# board_full.net
KiCad netlist of a schematic drawn in EAGLE
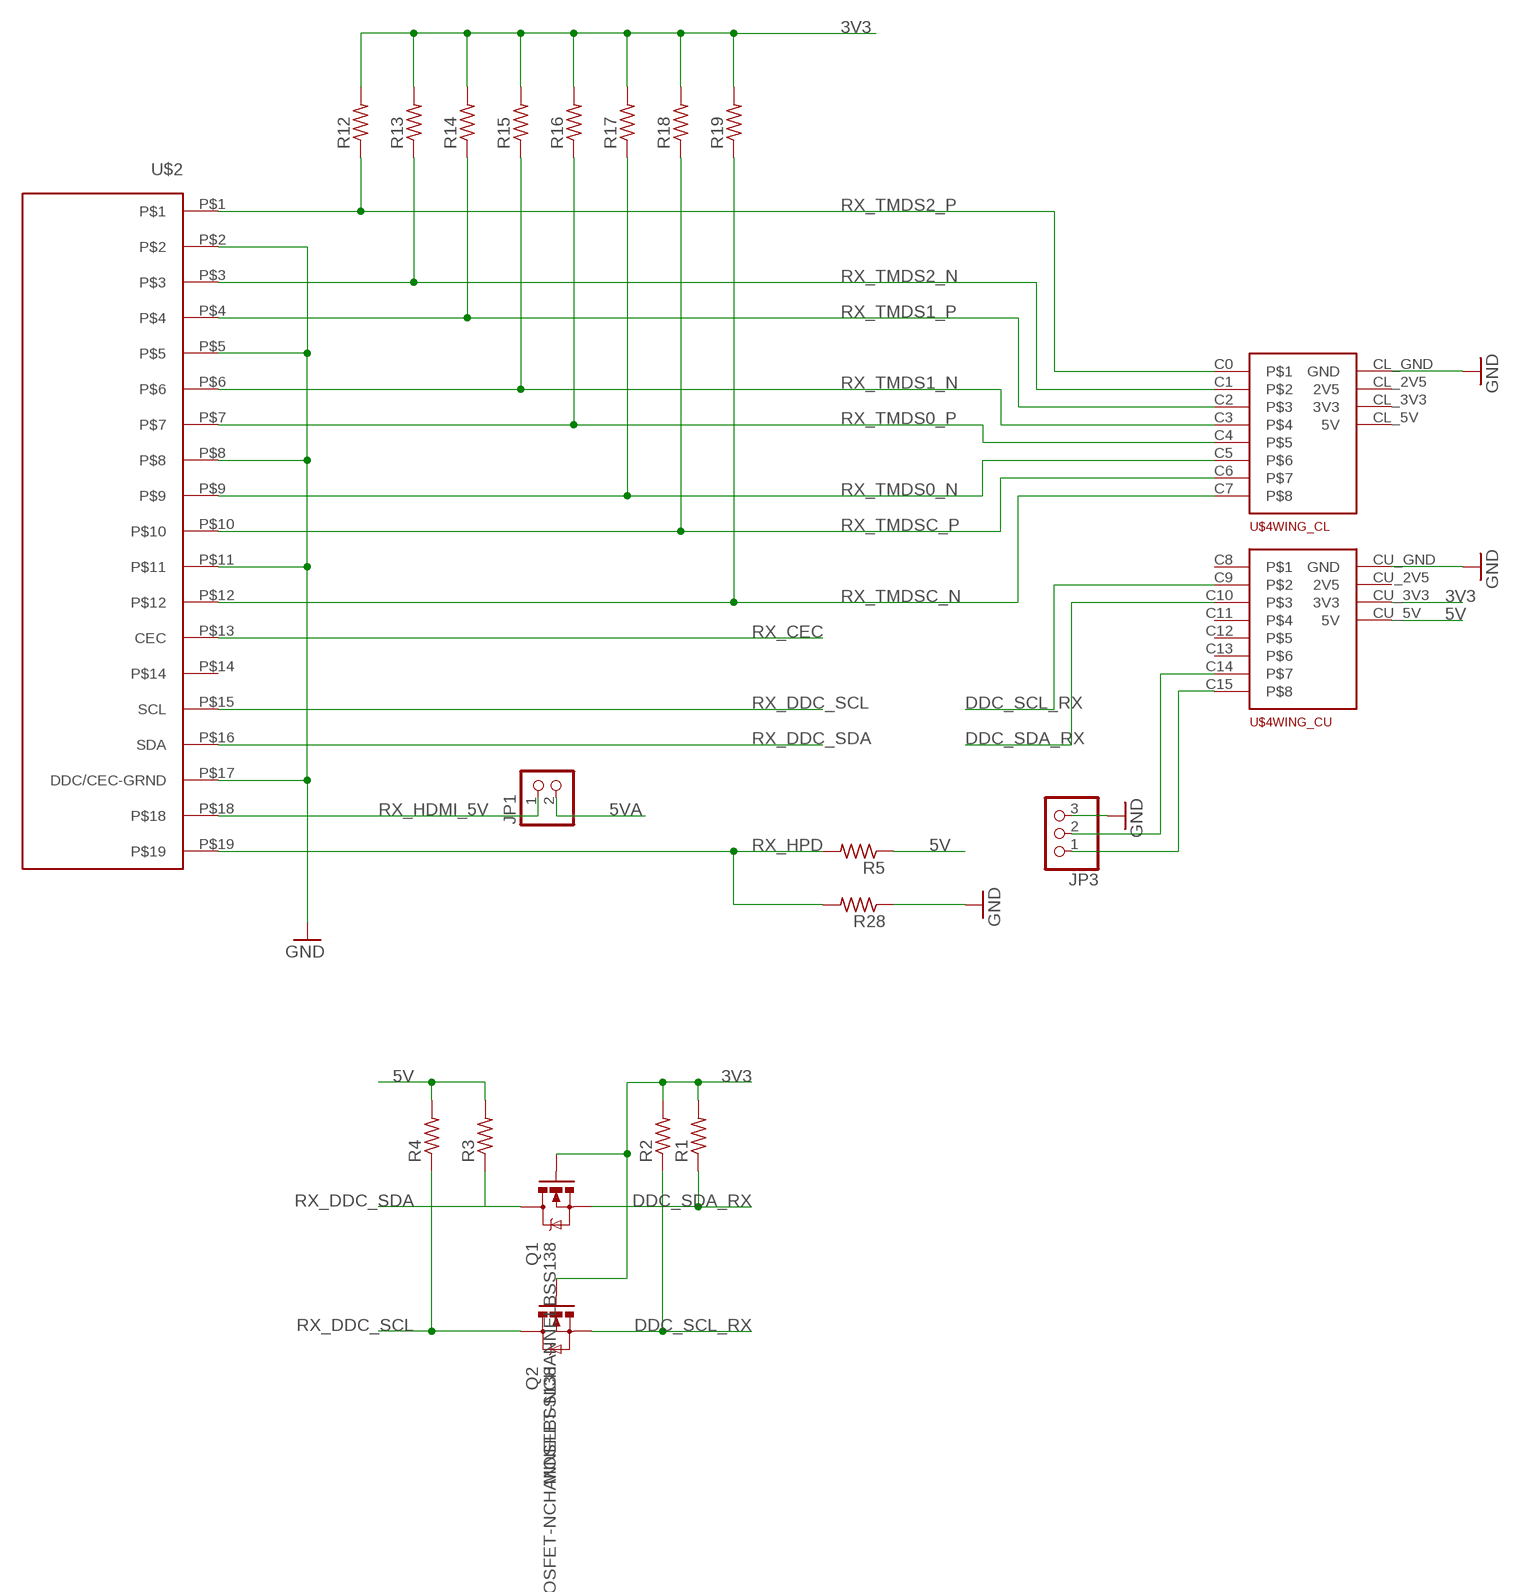
[diagram p0: schematic, sheet 1, part 1 of 2]
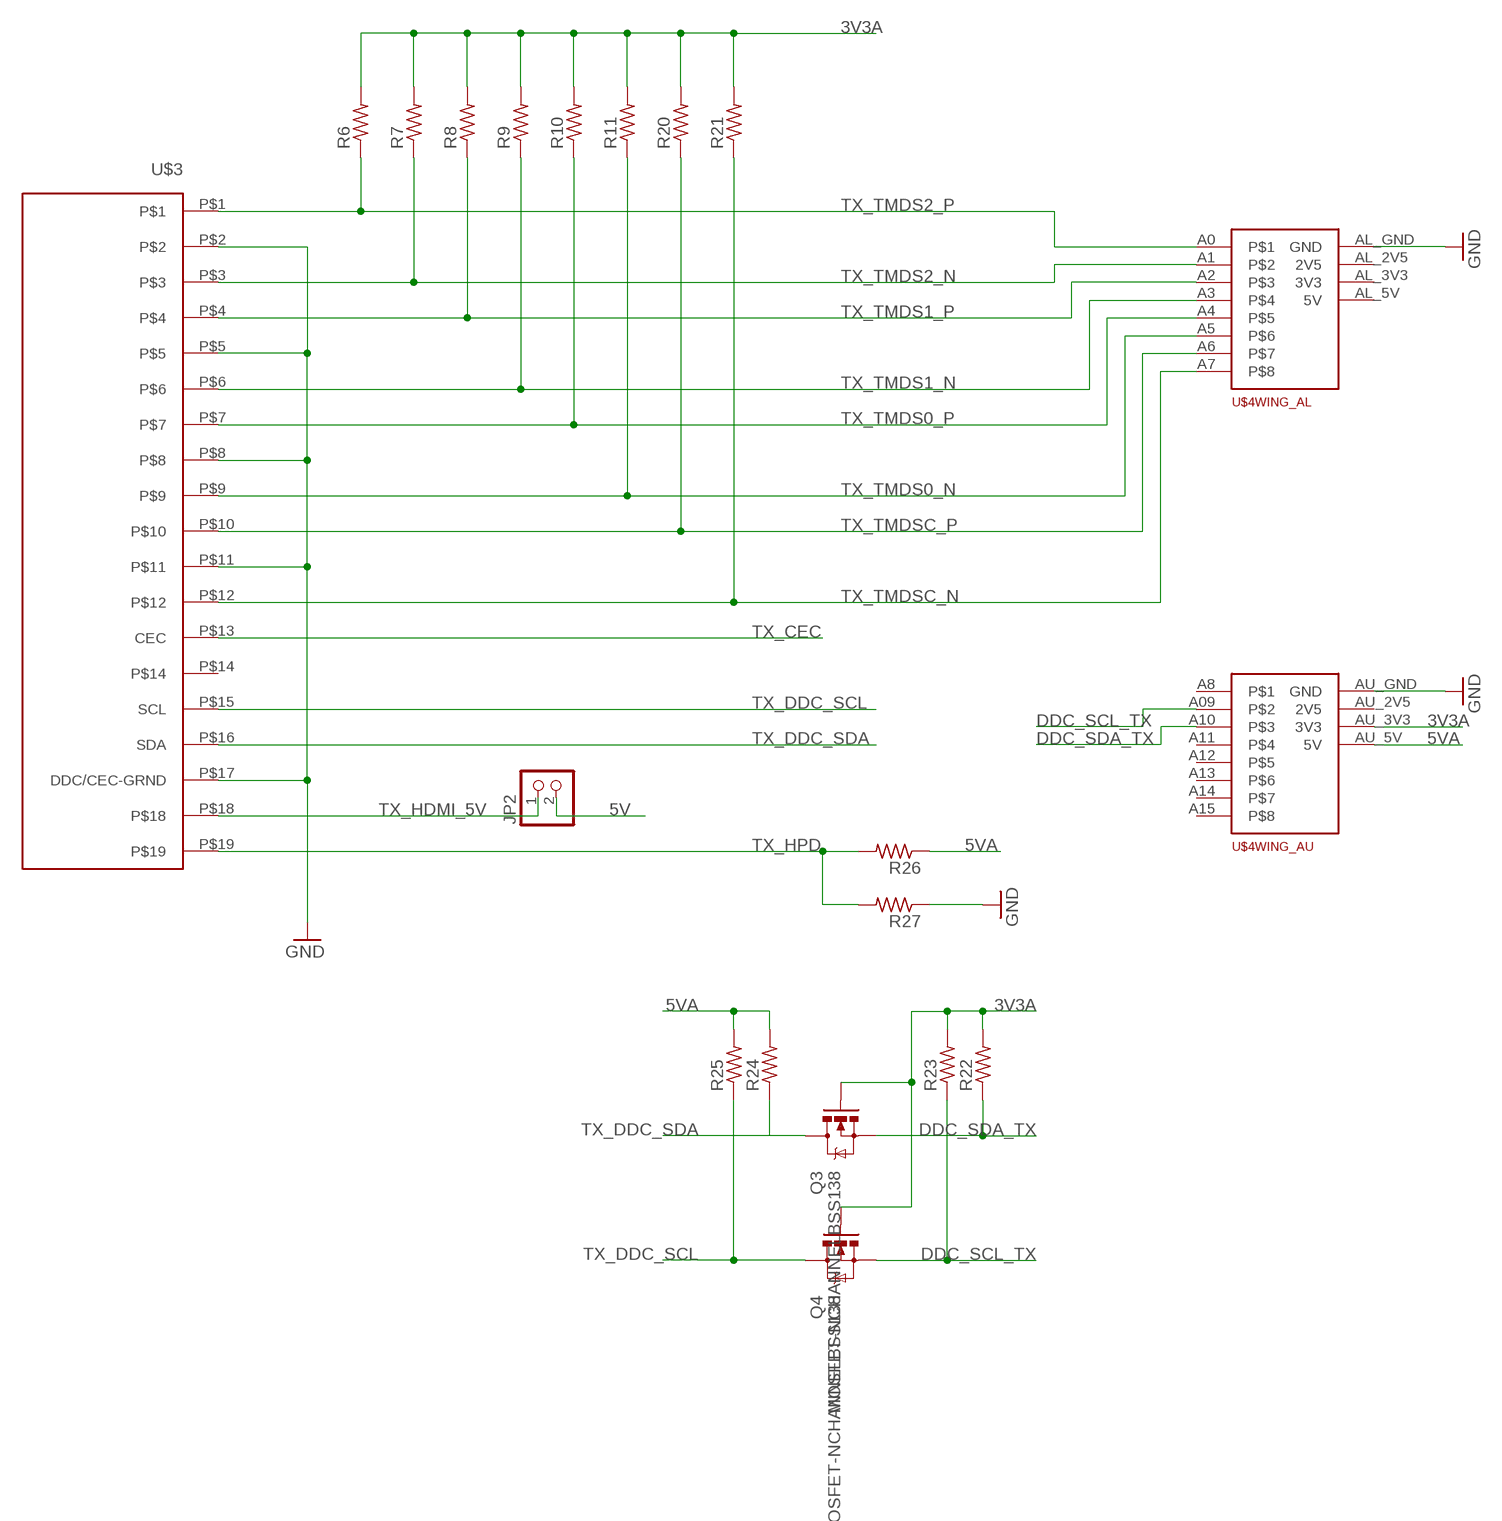
[diagram p1: schematic, sheet 1, part 2 of 2]

(export (version "E")
  (design (tool "Eeschema 10.0.6"))
  (components
    (comp (ref "JP1")
      (value "PINHD-1X2")
      (footprint "eagle-import:1X02")
      (libsource (lib "eagle-import") (part "PINHD-1X2"))
    )
    (comp (ref "JP2")
      (value "PINHD-1X2")
      (footprint "eagle-import:1X02")
      (libsource (lib "eagle-import") (part "PINHD-1X2"))
    )
    (comp (ref "JP3")
      (value "PINHD-1X3")
      (footprint "eagle-import:1X03")
      (libsource (lib "eagle-import") (part "PINHD-1X3"))
    )
    (comp (ref "Q1")
      (value "MOSFET-NCHANNELBSS138")
      (footprint "eagle-import:SOT23")
      (libsource (lib "eagle-import") (part "MOSFET-NCHANNELBSS138"))
    )
    (comp (ref "Q2")
      (value "MOSFET-NCHANNELBSS138")
      (footprint "eagle-import:SOT23")
      (libsource (lib "eagle-import") (part "MOSFET-NCHANNELBSS138"))
    )
    (comp (ref "Q3")
      (value "MOSFET-NCHANNELBSS138")
      (footprint "eagle-import:SOT23")
      (libsource (lib "eagle-import") (part "MOSFET-NCHANNELBSS138"))
    )
    (comp (ref "Q4")
      (value "MOSFET-NCHANNELBSS138")
      (footprint "eagle-import:SOT23")
      (libsource (lib "eagle-import") (part "MOSFET-NCHANNELBSS138"))
    )
    (comp (ref "R1")
      (value "R-US_R0805")
      (footprint "eagle-import:R0805")
      (libsource (lib "eagle-import") (part "R-US_R0805"))
    )
    (comp (ref "R2")
      (value "R-US_R0805")
      (footprint "eagle-import:R0805")
      (libsource (lib "eagle-import") (part "R-US_R0805"))
    )
    (comp (ref "R3")
      (value "R-US_R0805")
      (footprint "eagle-import:R0805")
      (libsource (lib "eagle-import") (part "R-US_R0805"))
    )
    (comp (ref "R4")
      (value "R-US_R0805")
      (footprint "eagle-import:R0805")
      (libsource (lib "eagle-import") (part "R-US_R0805"))
    )
    (comp (ref "R5")
      (value "R-US_R0805")
      (footprint "eagle-import:R0805")
      (libsource (lib "eagle-import") (part "R-US_R0805"))
    )
    (comp (ref "R6")
      (value "R-US_R0805")
      (footprint "eagle-import:R0805")
      (libsource (lib "eagle-import") (part "R-US_R0805"))
    )
    (comp (ref "R7")
      (value "R-US_R0805")
      (footprint "eagle-import:R0805")
      (libsource (lib "eagle-import") (part "R-US_R0805"))
    )
    (comp (ref "R8")
      (value "R-US_R0805")
      (footprint "eagle-import:R0805")
      (libsource (lib "eagle-import") (part "R-US_R0805"))
    )
    (comp (ref "R9")
      (value "R-US_R0805")
      (footprint "eagle-import:R0805")
      (libsource (lib "eagle-import") (part "R-US_R0805"))
    )
    (comp (ref "R10")
      (value "R-US_R0805")
      (footprint "eagle-import:R0805")
      (libsource (lib "eagle-import") (part "R-US_R0805"))
    )
    (comp (ref "R11")
      (value "R-US_R0805")
      (footprint "eagle-import:R0805")
      (libsource (lib "eagle-import") (part "R-US_R0805"))
    )
    (comp (ref "R12")
      (value "R-US_R0805")
      (footprint "eagle-import:R0805")
      (libsource (lib "eagle-import") (part "R-US_R0805"))
    )
    (comp (ref "R13")
      (value "R-US_R0805")
      (footprint "eagle-import:R0805")
      (libsource (lib "eagle-import") (part "R-US_R0805"))
    )
    (comp (ref "R14")
      (value "R-US_R0805")
      (footprint "eagle-import:R0805")
      (libsource (lib "eagle-import") (part "R-US_R0805"))
    )
    (comp (ref "R15")
      (value "R-US_R0805")
      (footprint "eagle-import:R0805")
      (libsource (lib "eagle-import") (part "R-US_R0805"))
    )
    (comp (ref "R16")
      (value "R-US_R0805")
      (footprint "eagle-import:R0805")
      (libsource (lib "eagle-import") (part "R-US_R0805"))
    )
    (comp (ref "R17")
      (value "R-US_R0805")
      (footprint "eagle-import:R0805")
      (libsource (lib "eagle-import") (part "R-US_R0805"))
    )
    (comp (ref "R18")
      (value "R-US_R0805")
      (footprint "eagle-import:R0805")
      (libsource (lib "eagle-import") (part "R-US_R0805"))
    )
    (comp (ref "R19")
      (value "R-US_R0805")
      (footprint "eagle-import:R0805")
      (libsource (lib "eagle-import") (part "R-US_R0805"))
    )
    (comp (ref "R20")
      (value "R-US_R0805")
      (footprint "eagle-import:R0805")
      (libsource (lib "eagle-import") (part "R-US_R0805"))
    )
    (comp (ref "R21")
      (value "R-US_R0805")
      (footprint "eagle-import:R0805")
      (libsource (lib "eagle-import") (part "R-US_R0805"))
    )
    (comp (ref "R22")
      (value "R-US_R0805")
      (footprint "eagle-import:R0805")
      (libsource (lib "eagle-import") (part "R-US_R0805"))
    )
    (comp (ref "R23")
      (value "R-US_R0805")
      (footprint "eagle-import:R0805")
      (libsource (lib "eagle-import") (part "R-US_R0805"))
    )
    (comp (ref "R24")
      (value "R-US_R0805")
      (footprint "eagle-import:R0805")
      (libsource (lib "eagle-import") (part "R-US_R0805"))
    )
    (comp (ref "R25")
      (value "R-US_R0805")
      (footprint "eagle-import:R0805")
      (libsource (lib "eagle-import") (part "R-US_R0805"))
    )
    (comp (ref "R26")
      (value "R-US_R0805")
      (footprint "eagle-import:R0805")
      (libsource (lib "eagle-import") (part "R-US_R0805"))
    )
    (comp (ref "R27")
      (value "R-US_R0805")
      (footprint "eagle-import:R0805")
      (libsource (lib "eagle-import") (part "R-US_R0805"))
    )
    (comp (ref "R28")
      (value "R-US_R0805")
      (footprint "eagle-import:R0805")
      (libsource (lib "eagle-import") (part "R-US_R0805"))
    )
    (comp (ref "U$2")
      (value "HDMI-TYPE-A-RECEPTICALFCI10029449")
      (footprint "eagle-import:FCI-HDMI-TYPE-A-RECEPT")
      (libsource (lib "eagle-import") (part "HDMI-TYPE-A-RECEPTICALFCI10029449"))
    )
    (comp (ref "U$3")
      (value "HDMI-TYPE-A-RECEPTICALFCI10029449")
      (footprint "eagle-import:FCI-HDMI-TYPE-A-RECEPT")
      (libsource (lib "eagle-import") (part "HDMI-TYPE-A-RECEPTICALFCI10029449"))
    )
    (comp (ref "U$4")
      (value "PAPILIO48")
      (footprint "eagle-import:PAPILIO48")
      (libsource (lib "eagle-import") (part "PAPILIO48"))
    )
  )
  (nets
    (net (code "1") (name "/3V3") (class "Default")
      (node (ref "Q1") (pin "1") (pinfunction "G_1") (pintype "passive"))
      (node (ref "Q2") (pin "1") (pinfunction "G_1") (pintype "passive"))
      (node (ref "R1") (pin "2") (pinfunction "2_2") (pintype "passive"))
      (node (ref "R12") (pin "2") (pinfunction "2_2") (pintype "passive"))
      (node (ref "R13") (pin "2") (pinfunction "2_2") (pintype "passive"))
      (node (ref "R14") (pin "2") (pinfunction "2_2") (pintype "passive"))
      (node (ref "R15") (pin "2") (pinfunction "2_2") (pintype "passive"))
      (node (ref "R16") (pin "2") (pinfunction "2_2") (pintype "passive"))
      (node (ref "R17") (pin "2") (pinfunction "2_2") (pintype "passive"))
      (node (ref "R18") (pin "2") (pinfunction "2_2") (pintype "passive"))
      (node (ref "R19") (pin "2") (pinfunction "2_2") (pintype "passive"))
      (node (ref "R2") (pin "2") (pinfunction "2_2") (pintype "passive"))
      (node (ref "U$4") (pin "CU_3V3") (pinfunction "3V3_CU_3V3") (pintype "bidirectional"))
    )
    (net (code "2") (name "/3V3A") (class "Default")
      (node (ref "Q3") (pin "1") (pinfunction "G_1") (pintype "passive"))
      (node (ref "Q4") (pin "1") (pinfunction "G_1") (pintype "passive"))
      (node (ref "R10") (pin "2") (pinfunction "2_2") (pintype "passive"))
      (node (ref "R11") (pin "2") (pinfunction "2_2") (pintype "passive"))
      (node (ref "R20") (pin "2") (pinfunction "2_2") (pintype "passive"))
      (node (ref "R21") (pin "2") (pinfunction "2_2") (pintype "passive"))
      (node (ref "R22") (pin "2") (pinfunction "2_2") (pintype "passive"))
      (node (ref "R23") (pin "2") (pinfunction "2_2") (pintype "passive"))
      (node (ref "R6") (pin "2") (pinfunction "2_2") (pintype "passive"))
      (node (ref "R7") (pin "2") (pinfunction "2_2") (pintype "passive"))
      (node (ref "R8") (pin "2") (pinfunction "2_2") (pintype "passive"))
      (node (ref "R9") (pin "2") (pinfunction "2_2") (pintype "passive"))
      (node (ref "U$4") (pin "AU_3V3") (pinfunction "3V3_AU_3V3") (pintype "bidirectional"))
    )
    (net (code "3") (name "/5V") (class "Default")
      (node (ref "JP2") (pin "2") (pinfunction "2_2") (pintype "passive"))
      (node (ref "R3") (pin "2") (pinfunction "2_2") (pintype "passive"))
      (node (ref "R4") (pin "2") (pinfunction "2_2") (pintype "passive"))
      (node (ref "R5") (pin "1") (pinfunction "1_1") (pintype "passive"))
      (node (ref "U$4") (pin "CU_5V") (pinfunction "5V_CU_5V") (pintype "bidirectional"))
    )
    (net (code "4") (name "/5VA") (class "Default")
      (node (ref "JP1") (pin "2") (pinfunction "2_2") (pintype "passive"))
      (node (ref "R24") (pin "2") (pinfunction "2_2") (pintype "passive"))
      (node (ref "R25") (pin "2") (pinfunction "2_2") (pintype "passive"))
      (node (ref "R26") (pin "1") (pinfunction "1_1") (pintype "passive"))
      (node (ref "U$4") (pin "AU_5V") (pinfunction "5V_AU_5V") (pintype "bidirectional"))
    )
    (net (code "5") (name "/DDC_SCL_RX") (class "Default")
      (node (ref "Q2") (pin "2") (pinfunction "S_2") (pintype "passive"))
      (node (ref "R2") (pin "1") (pinfunction "1_1") (pintype "passive"))
      (node (ref "U$4") (pin "C9") (pinfunction "P$2_C9") (pintype "bidirectional"))
    )
    (net (code "6") (name "/DDC_SCL_TX") (class "Default")
      (node (ref "Q4") (pin "2") (pinfunction "S_2") (pintype "passive"))
      (node (ref "R23") (pin "1") (pinfunction "1_1") (pintype "passive"))
      (node (ref "U$4") (pin "A09") (pinfunction "P$2_A09") (pintype "bidirectional"))
    )
    (net (code "7") (name "/DDC_SDA_RX") (class "Default")
      (node (ref "Q1") (pin "2") (pinfunction "S_2") (pintype "passive"))
      (node (ref "R1") (pin "1") (pinfunction "1_1") (pintype "passive"))
      (node (ref "U$4") (pin "C10") (pinfunction "P$3_C10") (pintype "bidirectional"))
    )
    (net (code "8") (name "/DDC_SDA_TX") (class "Default")
      (node (ref "Q3") (pin "2") (pinfunction "S_2") (pintype "passive"))
      (node (ref "R22") (pin "1") (pinfunction "1_1") (pintype "passive"))
      (node (ref "U$4") (pin "A10") (pinfunction "P$3_A10") (pintype "bidirectional"))
    )
    (net (code "9") (name "/RX_CEC") (class "Default")
      (node (ref "U$2") (pin "P$13") (pinfunction "CEC_P$13") (pintype "bidirectional"))
    )
    (net (code "10") (name "/RX_DDC_SCL") (class "Default")
      (node (ref "Q2") (pin "3") (pinfunction "D_3") (pintype "passive"))
      (node (ref "R4") (pin "1") (pinfunction "1_1") (pintype "passive"))
      (node (ref "U$2") (pin "P$15") (pinfunction "SCL_P$15") (pintype "bidirectional"))
    )
    (net (code "11") (name "/RX_DDC_SDA") (class "Default")
      (node (ref "Q1") (pin "3") (pinfunction "D_3") (pintype "passive"))
      (node (ref "R3") (pin "1") (pinfunction "1_1") (pintype "passive"))
      (node (ref "U$2") (pin "P$16") (pinfunction "SDA_P$16") (pintype "bidirectional"))
    )
    (net (code "12") (name "/RX_HDMI_5V") (class "Default")
      (node (ref "JP1") (pin "1") (pinfunction "1_1") (pintype "passive"))
      (node (ref "U$2") (pin "P$18") (pinfunction "P$18_P$18") (pintype "bidirectional"))
    )
    (net (code "13") (name "/RX_HPD") (class "Default")
      (node (ref "R28") (pin "2") (pinfunction "2_2") (pintype "passive"))
      (node (ref "R5") (pin "2") (pinfunction "2_2") (pintype "passive"))
      (node (ref "U$2") (pin "P$19") (pinfunction "P$19_P$19") (pintype "bidirectional"))
    )
    (net (code "14") (name "/RX_TMDS0_N") (class "Default")
      (node (ref "R17") (pin "1") (pinfunction "1_1") (pintype "passive"))
      (node (ref "U$2") (pin "P$9") (pinfunction "P$9_P$9") (pintype "bidirectional"))
      (node (ref "U$4") (pin "C5") (pinfunction "P$6_C5") (pintype "bidirectional"))
    )
    (net (code "15") (name "/RX_TMDS0_P") (class "Default")
      (node (ref "R16") (pin "1") (pinfunction "1_1") (pintype "passive"))
      (node (ref "U$2") (pin "P$7") (pinfunction "P$7_P$7") (pintype "bidirectional"))
      (node (ref "U$4") (pin "C4") (pinfunction "P$5_C4") (pintype "bidirectional"))
    )
    (net (code "16") (name "/RX_TMDS1_N") (class "Default")
      (node (ref "R15") (pin "1") (pinfunction "1_1") (pintype "passive"))
      (node (ref "U$2") (pin "P$6") (pinfunction "P$6_P$6") (pintype "bidirectional"))
      (node (ref "U$4") (pin "C3") (pinfunction "P$4_C3") (pintype "bidirectional"))
    )
    (net (code "17") (name "/RX_TMDS1_P") (class "Default")
      (node (ref "R14") (pin "1") (pinfunction "1_1") (pintype "passive"))
      (node (ref "U$2") (pin "P$4") (pinfunction "P$4_P$4") (pintype "bidirectional"))
      (node (ref "U$4") (pin "C2") (pinfunction "P$3_C2") (pintype "bidirectional"))
    )
    (net (code "18") (name "/RX_TMDS2_N") (class "Default")
      (node (ref "R13") (pin "1") (pinfunction "1_1") (pintype "passive"))
      (node (ref "U$2") (pin "P$3") (pinfunction "P$3_P$3") (pintype "bidirectional"))
      (node (ref "U$4") (pin "C1") (pinfunction "P$2_C1") (pintype "bidirectional"))
    )
    (net (code "19") (name "/RX_TMDS2_P") (class "Default")
      (node (ref "R12") (pin "1") (pinfunction "1_1") (pintype "passive"))
      (node (ref "U$2") (pin "P$1") (pinfunction "P$1_P$1") (pintype "bidirectional"))
      (node (ref "U$4") (pin "C0") (pinfunction "P$1_C0") (pintype "bidirectional"))
    )
    (net (code "20") (name "/RX_TMDSC_N") (class "Default")
      (node (ref "R19") (pin "1") (pinfunction "1_1") (pintype "passive"))
      (node (ref "U$2") (pin "P$12") (pinfunction "P$12_P$12") (pintype "bidirectional"))
      (node (ref "U$4") (pin "C7") (pinfunction "P$8_C7") (pintype "bidirectional"))
    )
    (net (code "21") (name "/RX_TMDSC_P") (class "Default")
      (node (ref "R18") (pin "1") (pinfunction "1_1") (pintype "passive"))
      (node (ref "U$2") (pin "P$10") (pinfunction "P$10_P$10") (pintype "bidirectional"))
      (node (ref "U$4") (pin "C6") (pinfunction "P$7_C6") (pintype "bidirectional"))
    )
    (net (code "22") (name "/TX_CEC") (class "Default")
      (node (ref "U$3") (pin "P$13") (pinfunction "CEC_P$13") (pintype "bidirectional"))
    )
    (net (code "23") (name "/TX_DDC_SCL") (class "Default")
      (node (ref "Q4") (pin "3") (pinfunction "D_3") (pintype "passive"))
      (node (ref "R25") (pin "1") (pinfunction "1_1") (pintype "passive"))
      (node (ref "U$3") (pin "P$15") (pinfunction "SCL_P$15") (pintype "bidirectional"))
    )
    (net (code "24") (name "/TX_DDC_SDA") (class "Default")
      (node (ref "Q3") (pin "3") (pinfunction "D_3") (pintype "passive"))
      (node (ref "R24") (pin "1") (pinfunction "1_1") (pintype "passive"))
      (node (ref "U$3") (pin "P$16") (pinfunction "SDA_P$16") (pintype "bidirectional"))
    )
    (net (code "25") (name "/TX_HDMI_5V") (class "Default")
      (node (ref "JP2") (pin "1") (pinfunction "1_1") (pintype "passive"))
      (node (ref "U$3") (pin "P$18") (pinfunction "P$18_P$18") (pintype "bidirectional"))
    )
    (net (code "26") (name "/TX_HPD") (class "Default")
      (node (ref "R26") (pin "2") (pinfunction "2_2") (pintype "passive"))
      (node (ref "R27") (pin "2") (pinfunction "2_2") (pintype "passive"))
      (node (ref "U$3") (pin "P$19") (pinfunction "P$19_P$19") (pintype "bidirectional"))
    )
    (net (code "27") (name "/TX_TMDS0_N") (class "Default")
      (node (ref "R11") (pin "1") (pinfunction "1_1") (pintype "passive"))
      (node (ref "U$3") (pin "P$9") (pinfunction "P$9_P$9") (pintype "bidirectional"))
      (node (ref "U$4") (pin "A5") (pinfunction "P$6_A5") (pintype "bidirectional"))
    )
    (net (code "28") (name "/TX_TMDS0_P") (class "Default")
      (node (ref "R10") (pin "1") (pinfunction "1_1") (pintype "passive"))
      (node (ref "U$3") (pin "P$7") (pinfunction "P$7_P$7") (pintype "bidirectional"))
      (node (ref "U$4") (pin "A4") (pinfunction "P$5_A4") (pintype "bidirectional"))
    )
    (net (code "29") (name "/TX_TMDS1_N") (class "Default")
      (node (ref "R9") (pin "1") (pinfunction "1_1") (pintype "passive"))
      (node (ref "U$3") (pin "P$6") (pinfunction "P$6_P$6") (pintype "bidirectional"))
      (node (ref "U$4") (pin "A3") (pinfunction "P$4_A3") (pintype "bidirectional"))
    )
    (net (code "30") (name "/TX_TMDS1_P") (class "Default")
      (node (ref "R8") (pin "1") (pinfunction "1_1") (pintype "passive"))
      (node (ref "U$3") (pin "P$4") (pinfunction "P$4_P$4") (pintype "bidirectional"))
      (node (ref "U$4") (pin "A2") (pinfunction "P$3_A2") (pintype "bidirectional"))
    )
    (net (code "31") (name "/TX_TMDS2_N") (class "Default")
      (node (ref "R7") (pin "1") (pinfunction "1_1") (pintype "passive"))
      (node (ref "U$3") (pin "P$3") (pinfunction "P$3_P$3") (pintype "bidirectional"))
      (node (ref "U$4") (pin "A1") (pinfunction "P$2_A1") (pintype "bidirectional"))
    )
    (net (code "32") (name "/TX_TMDS2_P") (class "Default")
      (node (ref "R6") (pin "1") (pinfunction "1_1") (pintype "passive"))
      (node (ref "U$3") (pin "P$1") (pinfunction "P$1_P$1") (pintype "bidirectional"))
      (node (ref "U$4") (pin "A0") (pinfunction "P$1_A0") (pintype "bidirectional"))
    )
    (net (code "33") (name "/TX_TMDSC_N") (class "Default")
      (node (ref "R21") (pin "1") (pinfunction "1_1") (pintype "passive"))
      (node (ref "U$3") (pin "P$12") (pinfunction "P$12_P$12") (pintype "bidirectional"))
      (node (ref "U$4") (pin "A7") (pinfunction "P$8_A7") (pintype "bidirectional"))
    )
    (net (code "34") (name "/TX_TMDSC_P") (class "Default")
      (node (ref "R20") (pin "1") (pinfunction "1_1") (pintype "passive"))
      (node (ref "U$3") (pin "P$10") (pinfunction "P$10_P$10") (pintype "bidirectional"))
      (node (ref "U$4") (pin "A6") (pinfunction "P$7_A6") (pintype "bidirectional"))
    )
    (net (code "35") (name "GND") (class "Default")
      (node (ref "JP3") (pin "3") (pinfunction "3_3") (pintype "passive"))
      (node (ref "R27") (pin "1") (pinfunction "1_1") (pintype "passive"))
      (node (ref "R28") (pin "1") (pinfunction "1_1") (pintype "passive"))
      (node (ref "U$2") (pin "P$11") (pinfunction "P$11_P$11") (pintype "bidirectional"))
      (node (ref "U$2") (pin "P$17") (pinfunction "DDC/CEC-GRND_P$17") (pintype "bidirectional"))
      (node (ref "U$2") (pin "P$2") (pinfunction "P$2_P$2") (pintype "bidirectional"))
      (node (ref "U$2") (pin "P$5") (pinfunction "P$5_P$5") (pintype "bidirectional"))
      (node (ref "U$2") (pin "P$8") (pinfunction "P$8_P$8") (pintype "bidirectional"))
      (node (ref "U$3") (pin "P$11") (pinfunction "P$11_P$11") (pintype "bidirectional"))
      (node (ref "U$3") (pin "P$17") (pinfunction "DDC/CEC-GRND_P$17") (pintype "bidirectional"))
      (node (ref "U$3") (pin "P$2") (pinfunction "P$2_P$2") (pintype "bidirectional"))
      (node (ref "U$3") (pin "P$5") (pinfunction "P$5_P$5") (pintype "bidirectional"))
      (node (ref "U$3") (pin "P$8") (pinfunction "P$8_P$8") (pintype "bidirectional"))
      (node (ref "U$4") (pin "AL_GND") (pinfunction "GND_AL_GND") (pintype "bidirectional"))
      (node (ref "U$4") (pin "AU_GND") (pinfunction "GND_AU_GND") (pintype "bidirectional"))
      (node (ref "U$4") (pin "CL_GND") (pinfunction "GND_CL_GND") (pintype "bidirectional"))
      (node (ref "U$4") (pin "CU_GND") (pinfunction "GND_CU_GND") (pintype "bidirectional"))
    )
    (net (code "36") (name "Net-(U$4D-P$7)") (class "Default")
      (node (ref "JP3") (pin "2") (pinfunction "2_2") (pintype "passive"))
      (node (ref "U$4") (pin "C14") (pinfunction "P$7_C14") (pintype "bidirectional"))
    )
    (net (code "37") (name "Net-(U$4D-P$8)") (class "Default")
      (node (ref "JP3") (pin "1") (pinfunction "1_1") (pintype "passive"))
      (node (ref "U$4") (pin "C15") (pinfunction "P$8_C15") (pintype "bidirectional"))
    )
    (net (code "38") (name "unconnected-(U$2-PadP$14)") (class "Default")
      (node (ref "U$2") (pin "P$14") (pinfunction "P$14_P$14") (pintype "bidirectional"))
    )
    (net (code "39") (name "unconnected-(U$3-PadP$14)") (class "Default")
      (node (ref "U$3") (pin "P$14") (pinfunction "P$14_P$14") (pintype "bidirectional"))
    )
    (net (code "40") (name "unconnected-(U$4A-2V5-PadAL_2V5)") (class "Default")
      (node (ref "U$4") (pin "AL_2V5") (pinfunction "2V5_AL_2V5") (pintype "bidirectional"))
    )
    (net (code "41") (name "unconnected-(U$4A-3V3-PadAL_3V3)") (class "Default")
      (node (ref "U$4") (pin "AL_3V3") (pinfunction "3V3_AL_3V3") (pintype "bidirectional"))
    )
    (net (code "42") (name "unconnected-(U$4A-5V-PadAL_5V)") (class "Default")
      (node (ref "U$4") (pin "AL_5V") (pinfunction "5V_AL_5V") (pintype "bidirectional"))
    )
    (net (code "43") (name "unconnected-(U$4B-2V5-PadAU_2V5)") (class "Default")
      (node (ref "U$4") (pin "AU_2V5") (pinfunction "2V5_AU_2V5") (pintype "bidirectional"))
    )
    (net (code "44") (name "unconnected-(U$4B-P$1-PadA8)") (class "Default")
      (node (ref "U$4") (pin "A8") (pinfunction "P$1_A8") (pintype "bidirectional"))
    )
    (net (code "45") (name "unconnected-(U$4B-P$4-PadA11)") (class "Default")
      (node (ref "U$4") (pin "A11") (pinfunction "P$4_A11") (pintype "bidirectional"))
    )
    (net (code "46") (name "unconnected-(U$4B-P$5-PadA12)") (class "Default")
      (node (ref "U$4") (pin "A12") (pinfunction "P$5_A12") (pintype "bidirectional"))
    )
    (net (code "47") (name "unconnected-(U$4B-P$6-PadA13)") (class "Default")
      (node (ref "U$4") (pin "A13") (pinfunction "P$6_A13") (pintype "bidirectional"))
    )
    (net (code "48") (name "unconnected-(U$4B-P$7-PadA14)") (class "Default")
      (node (ref "U$4") (pin "A14") (pinfunction "P$7_A14") (pintype "bidirectional"))
    )
    (net (code "49") (name "unconnected-(U$4B-P$8-PadA15)") (class "Default")
      (node (ref "U$4") (pin "A15") (pinfunction "P$8_A15") (pintype "bidirectional"))
    )
    (net (code "50") (name "unconnected-(U$4C-2V5-PadCL_2V5)") (class "Default")
      (node (ref "U$4") (pin "CL_2V5") (pinfunction "2V5_CL_2V5") (pintype "bidirectional"))
    )
    (net (code "51") (name "unconnected-(U$4C-3V3-PadCL_3V3)") (class "Default")
      (node (ref "U$4") (pin "CL_3V3") (pinfunction "3V3_CL_3V3") (pintype "bidirectional"))
    )
    (net (code "52") (name "unconnected-(U$4C-5V-PadCL_5V)") (class "Default")
      (node (ref "U$4") (pin "CL_5V") (pinfunction "5V_CL_5V") (pintype "bidirectional"))
    )
    (net (code "53") (name "unconnected-(U$4D-2V5-PadCU_2V5)") (class "Default")
      (node (ref "U$4") (pin "CU_2V5") (pinfunction "2V5_CU_2V5") (pintype "bidirectional"))
    )
    (net (code "54") (name "unconnected-(U$4D-P$1-PadC8)") (class "Default")
      (node (ref "U$4") (pin "C8") (pinfunction "P$1_C8") (pintype "bidirectional"))
    )
    (net (code "55") (name "unconnected-(U$4D-P$4-PadC11)") (class "Default")
      (node (ref "U$4") (pin "C11") (pinfunction "P$4_C11") (pintype "bidirectional"))
    )
    (net (code "56") (name "unconnected-(U$4D-P$5-PadC12)") (class "Default")
      (node (ref "U$4") (pin "C12") (pinfunction "P$5_C12") (pintype "bidirectional"))
    )
    (net (code "57") (name "unconnected-(U$4D-P$6-PadC13)") (class "Default")
      (node (ref "U$4") (pin "C13") (pinfunction "P$6_C13") (pintype "bidirectional"))
    )
  )
)
